# LED_12T.net
KiCad netlist of a schematic drawn in Altium Designer
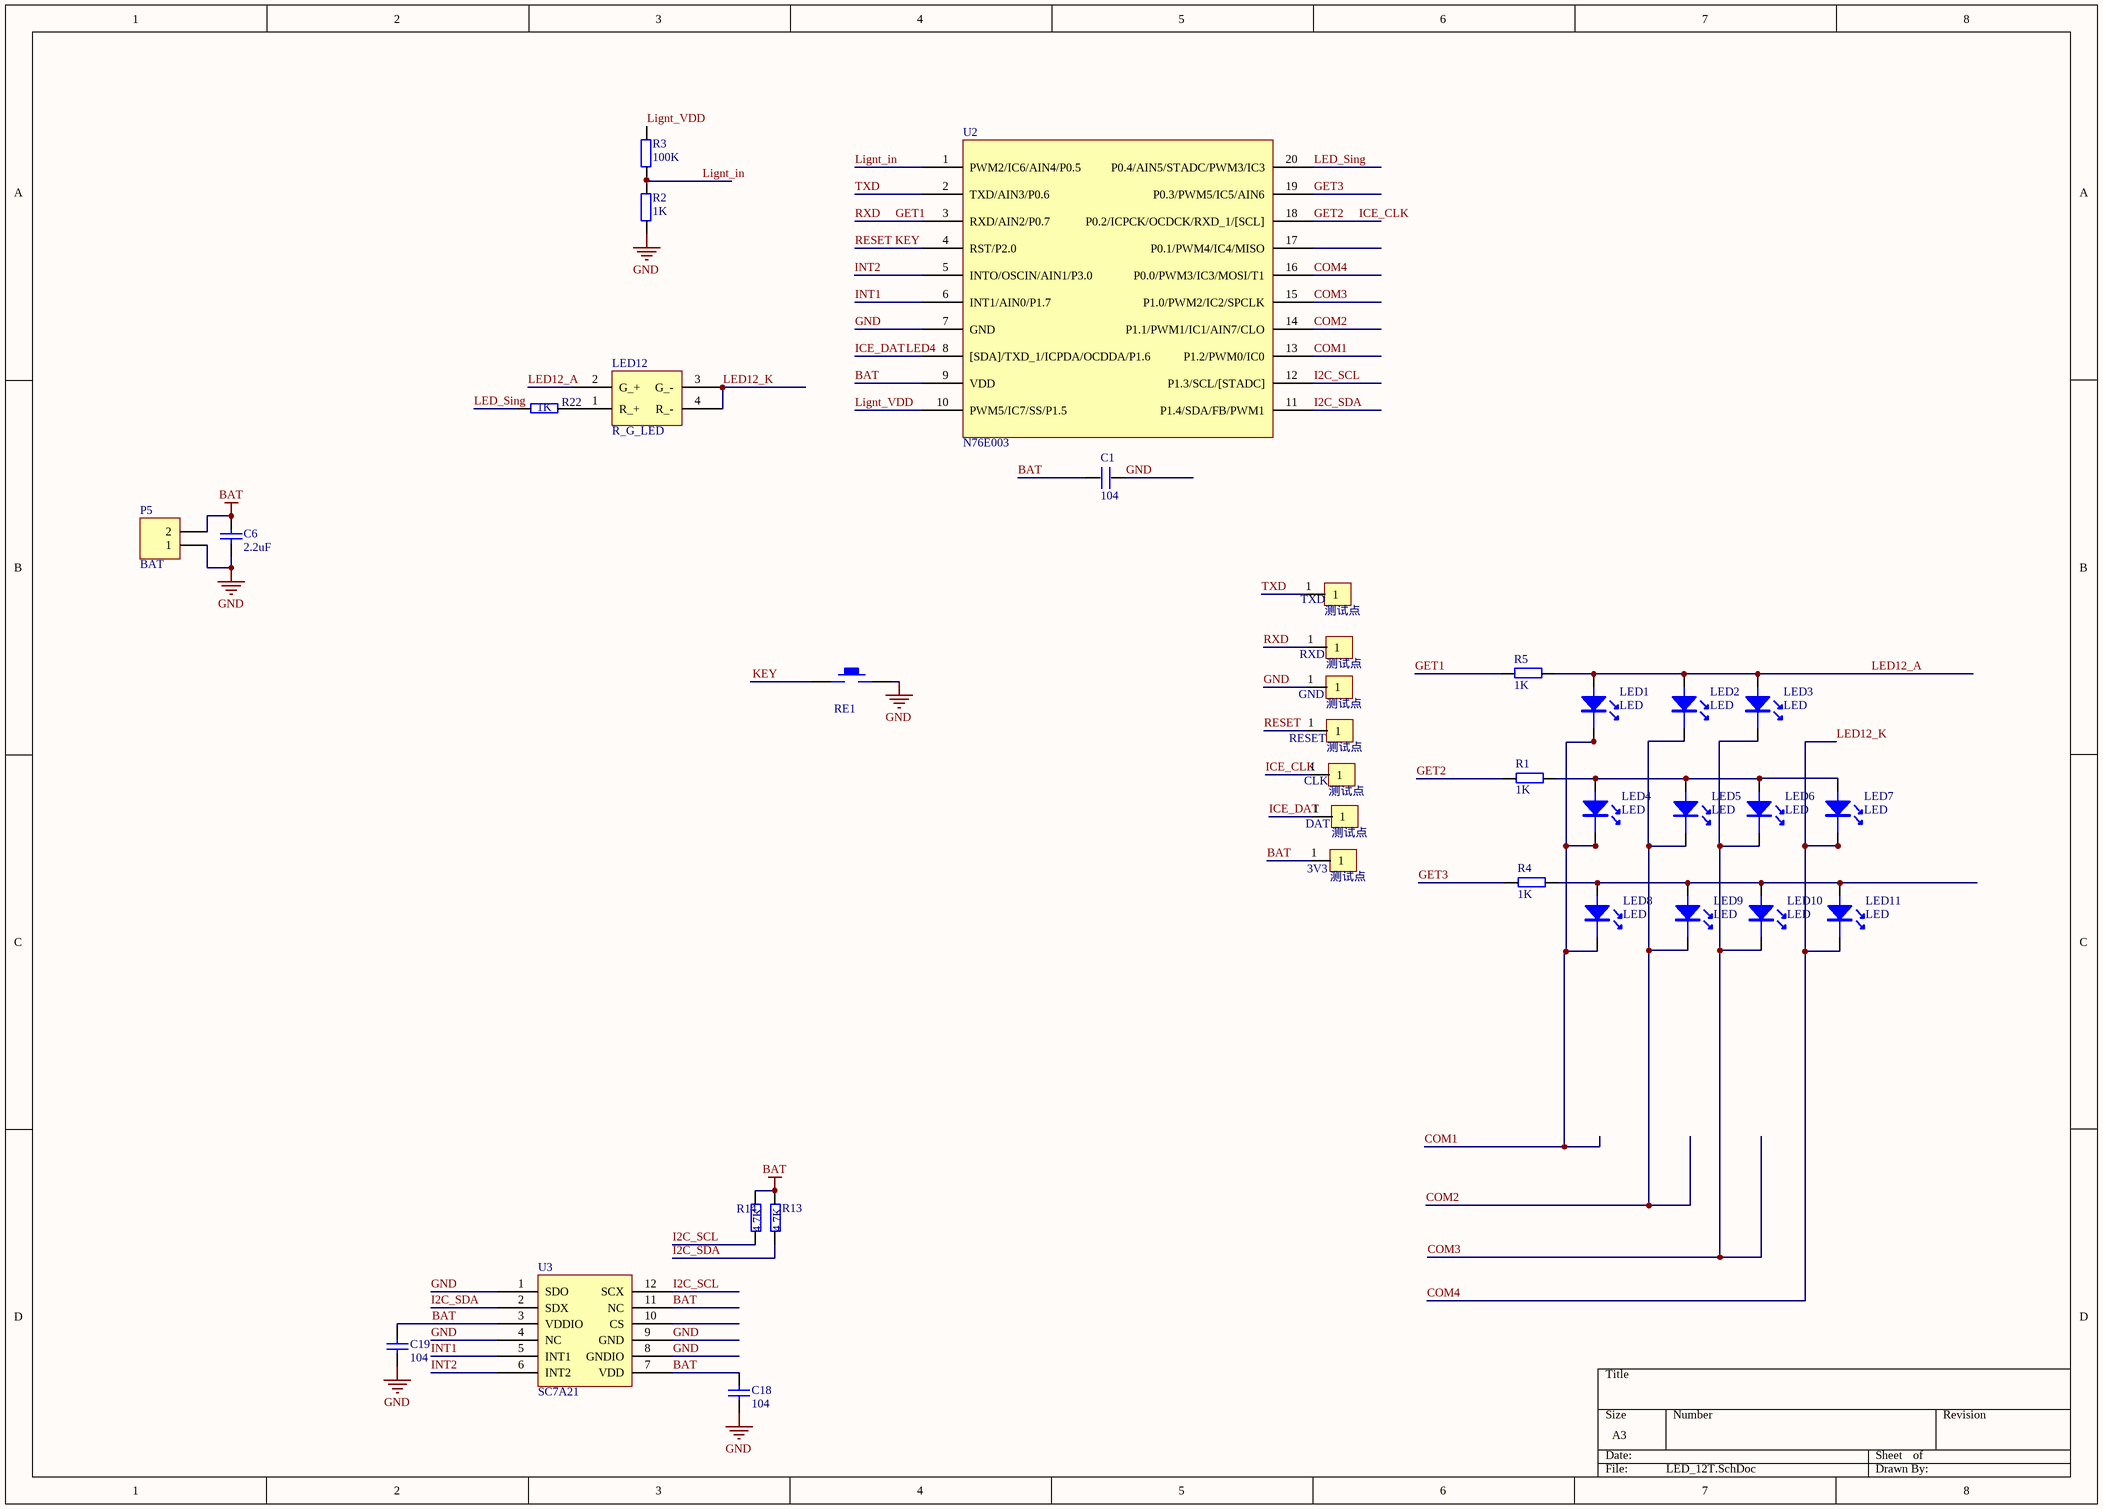
[diagram p0: LED_12T.SchDoc]

(export (version "E")
  (design (tool "Eeschema 10.0.6"))
  (components
    (comp (ref "3V3") (value "测试点") (footprint "测试点") (libsource (lib "元件") (part "测试点")))
    (comp (ref "C1") (value "104") (footprint "0603P") (libsource (lib "3.5TFTLCD封装库") (part "C")))
    (comp (ref "C6")
      (value "2.2uF")
      (footprint "0603_C")
      (description "Capacitor")
      (fields (field (name "PUBLISHER") "Altium Limited"))
      (libsource (lib "Miscellaneous Devices") (part "Cap"))
    )
    (comp (ref "C18")
      (value "104")
      (footprint "0402_C")
      (description "Capacitor")
      (fields (field (name "PUBLISHER") "Altium Limited"))
      (libsource (lib "Miscellaneous Devices") (part "Cap"))
    )
    (comp (ref "C19")
      (value "104")
      (footprint "0402_C")
      (description "Capacitor")
      (fields (field (name "PUBLISHER") "Altium Limited"))
      (libsource (lib "Miscellaneous Devices") (part "Cap"))
    )
    (comp (ref "CLK") (value "测试点") (footprint "测试点") (libsource (lib "元件") (part "测试点")))
    (comp (ref "DAT") (value "测试点") (footprint "测试点") (libsource (lib "元件") (part "测试点")))
    (comp (ref "GND") (value "测试点") (footprint "测试点") (libsource (lib "元件") (part "测试点")))
    (comp (ref "LED1") (value "LED") (footprint "0402_LED") (libsource (lib "*") (part "LED")))
    (comp (ref "LED2") (value "LED") (footprint "0402_LED") (libsource (lib "*") (part "LED")))
    (comp (ref "LED3") (value "LED") (footprint "0402_LED") (libsource (lib "*") (part "LED")))
    (comp (ref "LED4") (value "LED") (footprint "0402_LED") (libsource (lib "*") (part "LED")))
    (comp (ref "LED5") (value "LED") (footprint "0402_LED") (libsource (lib "*") (part "LED")))
    (comp (ref "LED6") (value "LED") (footprint "0402_LED") (libsource (lib "*") (part "LED")))
    (comp (ref "LED7") (value "LED") (footprint "0402_LED") (libsource (lib "*") (part "LED")))
    (comp (ref "LED8") (value "LED") (footprint "0402_LED") (libsource (lib "*") (part "LED")))
    (comp (ref "LED9") (value "LED") (footprint "0402_LED") (libsource (lib "*") (part "LED")))
    (comp (ref "LED10") (value "LED") (footprint "0402_LED") (libsource (lib "*") (part "LED")))
    (comp (ref "LED11") (value "LED") (footprint "0402_LED") (libsource (lib "*") (part "LED")))
    (comp (ref "LED12") (value "R_G_LED") (footprint "0603_R_G_LED") (libsource (lib "元件") (part "R_G_LED")))
    (comp (ref "P5")
      (value "BAT")
      (footprint "HDR1X2")
      (description "Header, 2-Pin")
      (fields (field (name "PUBLISHER") "Altium Limited"))
      (libsource (lib "Miscellaneous Connectors") (part "Header 2"))
    )
    (comp (ref "R1")
      (value "1K")
      (footprint "自画库1:0402_R")
      (libsource (lib "Explorer STM32F407封装库") (part "R"))
    )
    (comp (ref "R2")
      (value "1K")
      (footprint "自画库1:0603_R")
      (libsource (lib "Explorer STM32F407封装库") (part "R"))
    )
    (comp (ref "R3")
      (value "100K")
      (footprint "自画库1:0402_R")
      (libsource (lib "Explorer STM32F407封装库") (part "R"))
    )
    (comp (ref "R4")
      (value "1K")
      (footprint "自画库1:0402_R")
      (libsource (lib "Explorer STM32F407封装库") (part "R"))
    )
    (comp (ref "R5")
      (value "1K")
      (footprint "自画库1:0402_R")
      (libsource (lib "Explorer STM32F407封装库") (part "R"))
    )
    (comp (ref "R13")
      (value "4.7K")
      (footprint "自画库1:0402_R")
      (libsource (lib "Explorer STM32F407封装库") (part "R"))
    )
    (comp (ref "R14")
      (value "4.7K")
      (footprint "自画库1:0402_R")
      (libsource (lib "Explorer STM32F407封装库") (part "R"))
    )
    (comp (ref "R22")
      (value "1K")
      (footprint "自画库1:0402_R")
      (libsource (lib "Explorer STM32F407封装库") (part "R"))
    )
    (comp (ref "RE1")
      (value "KEY_M")
      (footprint "轻触开关 2x4")
      (libsource (lib "Explorer STM32F407封装库") (part "KEY_M"))
    )
    (comp (ref "RESET") (value "测试点") (footprint "测试点") (libsource (lib "元件") (part "测试点")))
    (comp (ref "RXD") (value "测试点") (footprint "测试点") (libsource (lib "元件") (part "测试点")))
    (comp (ref "TXD") (value "测试点") (footprint "测试点") (libsource (lib "元件") (part "测试点")))
    (comp (ref "U2") (value "N76E003") (footprint "STSOP20") (libsource (lib "元件") (part "N76E003")))
    (comp (ref "U3") (value "SC7A21") (footprint "自画库1:LGA-12-2*2*1") (libsource (lib "元件") (part "SC7A21")))
  )
  (nets
    (net (code "1") (name "/COM1") (class "Default")
      (node (ref "LED1") (pin "2") (pinfunction "K_2") (pintype "passive"))
      (node (ref "LED4") (pin "2") (pinfunction "K_2") (pintype "passive"))
      (node (ref "LED8") (pin "2") (pinfunction "K_2") (pintype "passive"))
      (node (ref "U2") (pin "13") (pinfunction "P1.2/PWM0/IC0_13") (pintype "passive"))
    )
    (net (code "2") (name "/COM2") (class "Default")
      (node (ref "LED2") (pin "2") (pinfunction "K_2") (pintype "passive"))
      (node (ref "LED5") (pin "2") (pinfunction "K_2") (pintype "passive"))
      (node (ref "LED9") (pin "2") (pinfunction "K_2") (pintype "passive"))
      (node (ref "U2") (pin "14") (pinfunction "P1.1/PWM1/IC1/AIN7/CLO_14") (pintype "passive"))
    )
    (net (code "3") (name "/COM3") (class "Default")
      (node (ref "LED10") (pin "2") (pinfunction "K_2") (pintype "passive"))
      (node (ref "LED3") (pin "2") (pinfunction "K_2") (pintype "passive"))
      (node (ref "LED6") (pin "2") (pinfunction "K_2") (pintype "passive"))
      (node (ref "U2") (pin "15") (pinfunction "P1.0/PWM2/IC2/SPCLK_15") (pintype "passive"))
    )
    (net (code "4") (name "/COM4") (class "Default")
      (node (ref "LED11") (pin "2") (pinfunction "K_2") (pintype "passive"))
      (node (ref "LED12") (pin "3") (pinfunction "G_-_3") (pintype "passive"))
      (node (ref "LED12") (pin "4") (pinfunction "R_-_4") (pintype "passive"))
      (node (ref "LED7") (pin "2") (pinfunction "K_2") (pintype "passive"))
      (node (ref "U2") (pin "16") (pinfunction "P0.0/PWM3/IC3/MOSI/T1_16") (pintype "passive"))
    )
    (net (code "5") (name "/GET1") (class "Default")
      (node (ref "R5") (pin "2") (pintype "passive"))
      (node (ref "RXD") (pin "1") (pinfunction "1_1") (pintype "passive"))
      (node (ref "U2") (pin "3") (pinfunction "RXD/AIN2/P0.7_3") (pintype "passive"))
    )
    (net (code "6") (name "/GET2") (class "Default")
      (node (ref "CLK") (pin "1") (pinfunction "1_1") (pintype "passive"))
      (node (ref "R1") (pin "2") (pintype "passive"))
      (node (ref "U2") (pin "18") (pinfunction "P0.2/ICPCK/OCDCK/RXD_1/[SCL]_18") (pintype "passive"))
    )
    (net (code "7") (name "/GET3") (class "Default")
      (node (ref "R4") (pin "2") (pintype "passive"))
      (node (ref "U2") (pin "19") (pinfunction "P0.3/PWM5/IC5/AIN6_19") (pintype "passive"))
    )
    (net (code "8") (name "/I2C_SCL") (class "Default")
      (node (ref "R14") (pin "1") (pintype "passive"))
      (node (ref "U2") (pin "12") (pinfunction "P1.3/SCL/[STADC]_12") (pintype "passive"))
      (node (ref "U3") (pin "12") (pinfunction "SCX_12") (pintype "passive"))
    )
    (net (code "9") (name "/I2C_SDA") (class "Default")
      (node (ref "R13") (pin "1") (pintype "passive"))
      (node (ref "U2") (pin "11") (pinfunction "P1.4/SDA/FB/PWM1_11") (pintype "passive"))
      (node (ref "U3") (pin "2") (pinfunction "SDX_2") (pintype "passive"))
    )
    (net (code "10") (name "/ICE_DAT") (class "Default")
      (node (ref "DAT") (pin "1") (pinfunction "1_1") (pintype "passive"))
      (node (ref "U2") (pin "8") (pinfunction "[SDA]/TXD_1/ICPDA/OCDDA/P1.6_8") (pintype "passive"))
    )
    (net (code "11") (name "/INT1") (class "Default")
      (node (ref "U2") (pin "6") (pinfunction "INT1/AIN0/P1.7_6") (pintype "passive"))
      (node (ref "U3") (pin "5") (pinfunction "INT1_5") (pintype "passive"))
    )
    (net (code "12") (name "/INT2") (class "Default")
      (node (ref "U2") (pin "5") (pinfunction "INTO/OSCIN/AIN1/P3.0_5") (pintype "passive"))
      (node (ref "U3") (pin "6") (pinfunction "INT2_6") (pintype "passive"))
    )
    (net (code "13") (name "/KEY") (class "Default")
      (node (ref "RE1") (pin "1") (pinfunction "1_1") (pintype "passive"))
      (node (ref "RESET") (pin "1") (pinfunction "1_1") (pintype "passive"))
      (node (ref "U2") (pin "4") (pinfunction "RST/P2.0_4") (pintype "passive"))
    )
    (net (code "14") (name "/LED12_A") (class "Default")
      (node (ref "LED1") (pin "1") (pinfunction "A_1") (pintype "passive"))
      (node (ref "LED12") (pin "2") (pinfunction "G_+_2") (pintype "passive"))
      (node (ref "LED2") (pin "1") (pinfunction "A_1") (pintype "passive"))
      (node (ref "LED3") (pin "1") (pinfunction "A_1") (pintype "passive"))
      (node (ref "R5") (pin "1") (pintype "passive"))
    )
    (net (code "15") (name "/LED_Sing") (class "Default")
      (node (ref "R22") (pin "2") (pintype "passive"))
      (node (ref "U2") (pin "20") (pinfunction "P0.4/AIN5/STADC/PWM3/IC3_20") (pintype "passive"))
    )
    (net (code "16") (name "/Lignt_VDD") (class "Default")
      (node (ref "R3") (pin "1") (pintype "passive"))
      (node (ref "U2") (pin "10") (pinfunction "PWM5/IC7/SS/P1.5_10") (pintype "passive"))
    )
    (net (code "17") (name "/Lignt_in") (class "Default")
      (node (ref "R2") (pin "1") (pintype "passive"))
      (node (ref "R3") (pin "2") (pintype "passive"))
      (node (ref "U2") (pin "1") (pinfunction "PWM2/IC6/AIN4/P0.5_1") (pintype "passive"))
    )
    (net (code "18") (name "/TXD") (class "Default")
      (node (ref "TXD") (pin "1") (pinfunction "1_1") (pintype "passive"))
      (node (ref "U2") (pin "2") (pinfunction "TXD/AIN3/P0.6_2") (pintype "passive"))
    )
    (net (code "19") (name "BAT") (class "Default")
      (node (ref "3V3") (pin "1") (pinfunction "1_1") (pintype "passive"))
      (node (ref "C1") (pin "2") (pintype "passive"))
      (node (ref "C18") (pin "1") (pinfunction "1_1") (pintype "passive"))
      (node (ref "C19") (pin "1") (pinfunction "1_1") (pintype "passive"))
      (node (ref "C6") (pin "2") (pinfunction "2_2") (pintype "passive"))
      (node (ref "P5") (pin "2") (pinfunction "2_2") (pintype "passive"))
      (node (ref "R13") (pin "2") (pintype "passive"))
      (node (ref "R14") (pin "2") (pintype "passive"))
      (node (ref "U2") (pin "9") (pinfunction "VDD_9") (pintype "passive"))
      (node (ref "U3") (pin "11") (pinfunction "NC_11") (pintype "passive"))
      (node (ref "U3") (pin "3") (pinfunction "VDDIO_3") (pintype "passive"))
      (node (ref "U3") (pin "7") (pinfunction "VDD_7") (pintype "passive"))
    )
    (net (code "20") (name "GND") (class "Default")
      (node (ref "C1") (pin "1") (pintype "passive"))
      (node (ref "C18") (pin "2") (pinfunction "2_2") (pintype "passive"))
      (node (ref "C19") (pin "2") (pinfunction "2_2") (pintype "passive"))
      (node (ref "C6") (pin "1") (pinfunction "1_1") (pintype "passive"))
      (node (ref "GND") (pin "1") (pinfunction "1_1") (pintype "passive"))
      (node (ref "P5") (pin "1") (pinfunction "1_1") (pintype "passive"))
      (node (ref "R2") (pin "2") (pintype "passive"))
      (node (ref "RE1") (pin "2") (pinfunction "2_2") (pintype "passive"))
      (node (ref "U2") (pin "7") (pinfunction "GND_7") (pintype "passive"))
      (node (ref "U3") (pin "1") (pinfunction "SDO_1") (pintype "passive"))
      (node (ref "U3") (pin "4") (pinfunction "NC_4") (pintype "passive"))
      (node (ref "U3") (pin "8") (pinfunction "GNDIO_8") (pintype "passive"))
      (node (ref "U3") (pin "9") (pinfunction "GND_9") (pintype "passive"))
    )
    (net (code "21") (name "Net-(LED4-A)") (class "Default")
      (node (ref "LED4") (pin "1") (pinfunction "A_1") (pintype "passive"))
      (node (ref "LED5") (pin "1") (pinfunction "A_1") (pintype "passive"))
      (node (ref "LED6") (pin "1") (pinfunction "A_1") (pintype "passive"))
      (node (ref "LED7") (pin "1") (pinfunction "A_1") (pintype "passive"))
      (node (ref "R1") (pin "1") (pintype "passive"))
    )
    (net (code "22") (name "Net-(LED10-A)") (class "Default")
      (node (ref "LED10") (pin "1") (pinfunction "A_1") (pintype "passive"))
      (node (ref "LED11") (pin "1") (pinfunction "A_1") (pintype "passive"))
      (node (ref "LED8") (pin "1") (pinfunction "A_1") (pintype "passive"))
      (node (ref "LED9") (pin "1") (pinfunction "A_1") (pintype "passive"))
      (node (ref "R4") (pin "1") (pintype "passive"))
    )
    (net (code "23") (name "Net-(LED12-R_+)") (class "Default")
      (node (ref "LED12") (pin "1") (pinfunction "R_+_1") (pintype "passive"))
      (node (ref "R22") (pin "1") (pintype "passive"))
    )
    (net (code "24") (name "unconnected-(U2-P0.1{slash}PWM4{slash}IC4{slash}MISO-Pad17)") (class "Default")
      (node (ref "U2") (pin "17") (pinfunction "P0.1/PWM4/IC4/MISO_17") (pintype "passive"))
    )
    (net (code "25") (name "unconnected-(U3-CS-Pad10)") (class "Default")
      (node (ref "U3") (pin "10") (pinfunction "CS_10") (pintype "passive"))
    )
  )
)
